# mcu_valdis3.net
KiCad netlist of a schematic drawn in Altium Designer
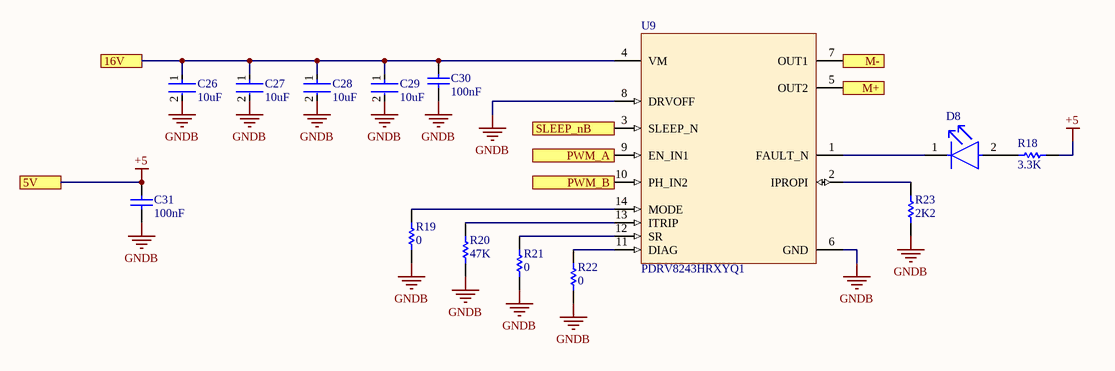
[diagram p0: mcu_valdis3.SchDoc]

(export (version "E")
  (design (tool "Eeschema 10.0.6"))
  (components
    (comp (ref "C26")
      (value "10uF")
      (footprint "FP-CL21-IPC_C")
      (description "CL21 Series 0805 22uF 25V ±20% Tolerance X5R Multilayer Ceramic Chip Capacitor")
      (libsource (lib "Altium Content Vault") (part "b4654b650e69147ec39a6b967a45e02"))
    )
    (comp (ref "C27")
      (value "10uF")
      (footprint "FP-CL21-IPC_C")
      (description "CL21 Series 0805 22uF 25V ±20% Tolerance X5R Multilayer Ceramic Chip Capacitor")
      (libsource (lib "Altium Content Vault") (part "b4654b650e69147ec39a6b967a45e02"))
    )
    (comp (ref "C28")
      (value "10uF")
      (footprint "FP-CL21-IPC_C")
      (description "CL21 Series 0805 22uF 25V ±20% Tolerance X5R Multilayer Ceramic Chip Capacitor")
      (libsource (lib "Altium Content Vault") (part "b4654b650e69147ec39a6b967a45e02"))
    )
    (comp (ref "C29")
      (value "10uF")
      (footprint "FP-CL21-IPC_C")
      (description "CL21 Series 0805 22uF 25V ±20% Tolerance X5R Multilayer Ceramic Chip Capacitor")
      (libsource (lib "Altium Content Vault") (part "b4654b650e69147ec39a6b967a45e02"))
    )
    (comp (ref "C30")
      (value "100nF")
      (footprint "CAPC1608X90X35ML10T15")
      (description "Chip Capacitor, 22 pF, +/- 5%, 50 V, -55 to 125 degC, 0603 (1608 Metric), RoHS, Tape and Reel")
      (fields (field (name "MANUFACTURER") "Murata"))
      (libsource (lib "Altium Content Vault") (part "CAP-NP-2"))
    )
    (comp (ref "C31")
      (value "100nF")
      (footprint "CAPC1608X90X35ML10T15")
      (description "Chip Capacitor, 22 pF, +/- 5%, 50 V, -55 to 125 degC, 0603 (1608 Metric), RoHS, Tape and Reel")
      (fields (field (name "MANUFACTURER") "Murata"))
      (libsource (lib "Altium Content Vault") (part "CAP-NP-2"))
    )
    (comp (ref "D8")
      (value "LTST-C191TBKT")
      (footprint "FP-LTST-C191TBKT-MFG")
      (description "LED BLUE CLEAR CHIP SMD")
      (libsource (lib "Altium Content Vault") (part "8706943c75ba83719d021d2fdc84c58"))
    )
    (comp (ref "R18")
      (value "3.3K")
      (footprint "RESC1609X50X30NL8T20")
      (description "Chip Resistor, 0 Ohm, Jumper, 100 mW, -55 to 155 degC, 0603 (1608 Metric), RoHS, Tape and Reel")
      (fields (field (name "MANUFACTURER") "Vishay Semiconductor"))
      (libsource (lib "Altium Content Vault") (part "RES-2"))
    )
    (comp (ref "R19")
      (value "0")
      (footprint "RESC1609X50X30NL8T20")
      (description "Chip Resistor, 0 Ohm, Jumper, 100 mW, -55 to 155 degC, 0603 (1608 Metric), RoHS, Tape and Reel")
      (fields (field (name "MANUFACTURER") "Vishay Semiconductor"))
      (libsource (lib "Altium Content Vault") (part "RES-2"))
    )
    (comp (ref "R20")
      (value "47K")
      (footprint "RESC1609X50X30NL8T20")
      (description "Chip Resistor, 0 Ohm, Jumper, 100 mW, -55 to 155 degC, 0603 (1608 Metric), RoHS, Tape and Reel")
      (fields (field (name "MANUFACTURER") "Vishay Semiconductor"))
      (libsource (lib "Altium Content Vault") (part "RES-2"))
    )
    (comp (ref "R21")
      (value "0")
      (footprint "RESC1609X50X30NL8T20")
      (description "Chip Resistor, 0 Ohm, Jumper, 100 mW, -55 to 155 degC, 0603 (1608 Metric), RoHS, Tape and Reel")
      (fields (field (name "MANUFACTURER") "Vishay Semiconductor"))
      (libsource (lib "Altium Content Vault") (part "RES-2"))
    )
    (comp (ref "R22")
      (value "0")
      (footprint "RESC1609X50X30NL8T20")
      (description "Chip Resistor, 0 Ohm, Jumper, 100 mW, -55 to 155 degC, 0603 (1608 Metric), RoHS, Tape and Reel")
      (fields (field (name "MANUFACTURER") "Vishay Semiconductor"))
      (libsource (lib "Altium Content Vault") (part "RES-2"))
    )
    (comp (ref "R23")
      (value "2K2")
      (footprint "RESC1609X50X30NL8T20")
      (description "Chip Resistor, 0 Ohm, Jumper, 100 mW, -55 to 155 degC, 0603 (1608 Metric), RoHS, Tape and Reel")
      (fields (field (name "MANUFACTURER") "Vishay Semiconductor"))
      (libsource (lib "Altium Content Vault") (part "RES-2"))
    )
    (comp (ref "U9")
      (value "PDRV8243HRXYQ1")
      (footprint "RXY0014A-MFG")
      (description "No Description Available")
      (fields (field (name "COPYRIGHT") "Copyright (C) 2022 Ultra Librarian. All rights reserved."))
      (libsource (lib "Valdis_Components") (part "PDRV8243HRXYQ1"))
    )
  )
  (nets
    (net (code "1") (name "+5") (class "Default")
      (node (ref "C31") (pin "2") (pinfunction "2_2") (pintype "passive"))
      (node (ref "R18") (pin "2") (pinfunction "2_2") (pintype "passive"))
    )
    (net (code "2") (name "/16V") (class "Default")
      (node (ref "C26") (pin "1") (pinfunction "1_1") (pintype "passive"))
      (node (ref "C27") (pin "1") (pinfunction "1_1") (pintype "passive"))
      (node (ref "C28") (pin "1") (pinfunction "1_1") (pintype "passive"))
      (node (ref "C29") (pin "1") (pinfunction "1_1") (pintype "passive"))
      (node (ref "C30") (pin "2") (pinfunction "2_2") (pintype "passive"))
      (node (ref "U9") (pin "4") (pinfunction "VM_4") (pintype "power_in"))
    )
    (net (code "3") (name "/M+") (class "Default")
      (node (ref "U9") (pin "5") (pinfunction "OUT2_5") (pintype "passive"))
    )
    (net (code "4") (name "/M-") (class "Default")
      (node (ref "U9") (pin "7") (pinfunction "OUT1_7") (pintype "passive"))
    )
    (net (code "5") (name "/PWM_A") (class "Default")
      (node (ref "U9") (pin "9") (pinfunction "EN_IN1_9") (pintype "input"))
    )
    (net (code "6") (name "/PWM_B") (class "Default")
      (node (ref "U9") (pin "10") (pinfunction "PH_IN2_10") (pintype "input"))
    )
    (net (code "7") (name "/SLEEP_nB") (class "Default")
      (node (ref "U9") (pin "3") (pinfunction "SLEEP_N_3") (pintype "input"))
    )
    (net (code "8") (name "GNDB") (class "Default")
      (node (ref "C26") (pin "2") (pinfunction "2_2") (pintype "passive"))
      (node (ref "C27") (pin "2") (pinfunction "2_2") (pintype "passive"))
      (node (ref "C28") (pin "2") (pinfunction "2_2") (pintype "passive"))
      (node (ref "C29") (pin "2") (pinfunction "2_2") (pintype "passive"))
      (node (ref "C30") (pin "1") (pinfunction "1_1") (pintype "passive"))
      (node (ref "C31") (pin "1") (pinfunction "1_1") (pintype "passive"))
      (node (ref "R19") (pin "1") (pinfunction "1_1") (pintype "passive"))
      (node (ref "R20") (pin "1") (pinfunction "1_1") (pintype "passive"))
      (node (ref "R21") (pin "1") (pinfunction "1_1") (pintype "passive"))
      (node (ref "R22") (pin "1") (pinfunction "1_1") (pintype "passive"))
      (node (ref "R23") (pin "1") (pinfunction "1_1") (pintype "passive"))
      (node (ref "U9") (pin "6") (pinfunction "GND_6") (pintype "power_in"))
      (node (ref "U9") (pin "8") (pinfunction "DRVOFF_8") (pintype "input"))
    )
    (net (code "9") (name "Net-(D8-A)") (class "Default")
      (node (ref "D8") (pin "2") (pinfunction "A_2") (pintype "passive"))
      (node (ref "R18") (pin "1") (pinfunction "1_1") (pintype "passive"))
    )
    (net (code "10") (name "Net-(D8-C)") (class "Default")
      (node (ref "D8") (pin "1") (pinfunction "C_1") (pintype "passive"))
      (node (ref "U9") (pin "1") (pinfunction "FAULT_N_1") (pintype "open_collector"))
    )
    (net (code "11") (name "Net-(U9-DIAG)") (class "Default")
      (node (ref "R22") (pin "2") (pinfunction "2_2") (pintype "passive"))
      (node (ref "U9") (pin "11") (pinfunction "DIAG_11") (pintype "input"))
    )
    (net (code "12") (name "Net-(U9-IPROPI)") (class "Default")
      (node (ref "R23") (pin "2") (pinfunction "2_2") (pintype "passive"))
      (node (ref "U9") (pin "2") (pinfunction "IPROPI_2") (pintype "bidirectional"))
    )
    (net (code "13") (name "Net-(U9-ITRIP)") (class "Default")
      (node (ref "R20") (pin "2") (pinfunction "2_2") (pintype "passive"))
      (node (ref "U9") (pin "13") (pinfunction "ITRIP_13") (pintype "input"))
    )
    (net (code "14") (name "Net-(U9-MODE)") (class "Default")
      (node (ref "R19") (pin "2") (pinfunction "2_2") (pintype "passive"))
      (node (ref "U9") (pin "14") (pinfunction "MODE_14") (pintype "input"))
    )
    (net (code "15") (name "Net-(U9-SR)") (class "Default")
      (node (ref "R21") (pin "2") (pinfunction "2_2") (pintype "passive"))
      (node (ref "U9") (pin "12") (pinfunction "SR_12") (pintype "input"))
    )
  )
)
